# simastep.net
KiCad netlist of a schematic drawn in EAGLE
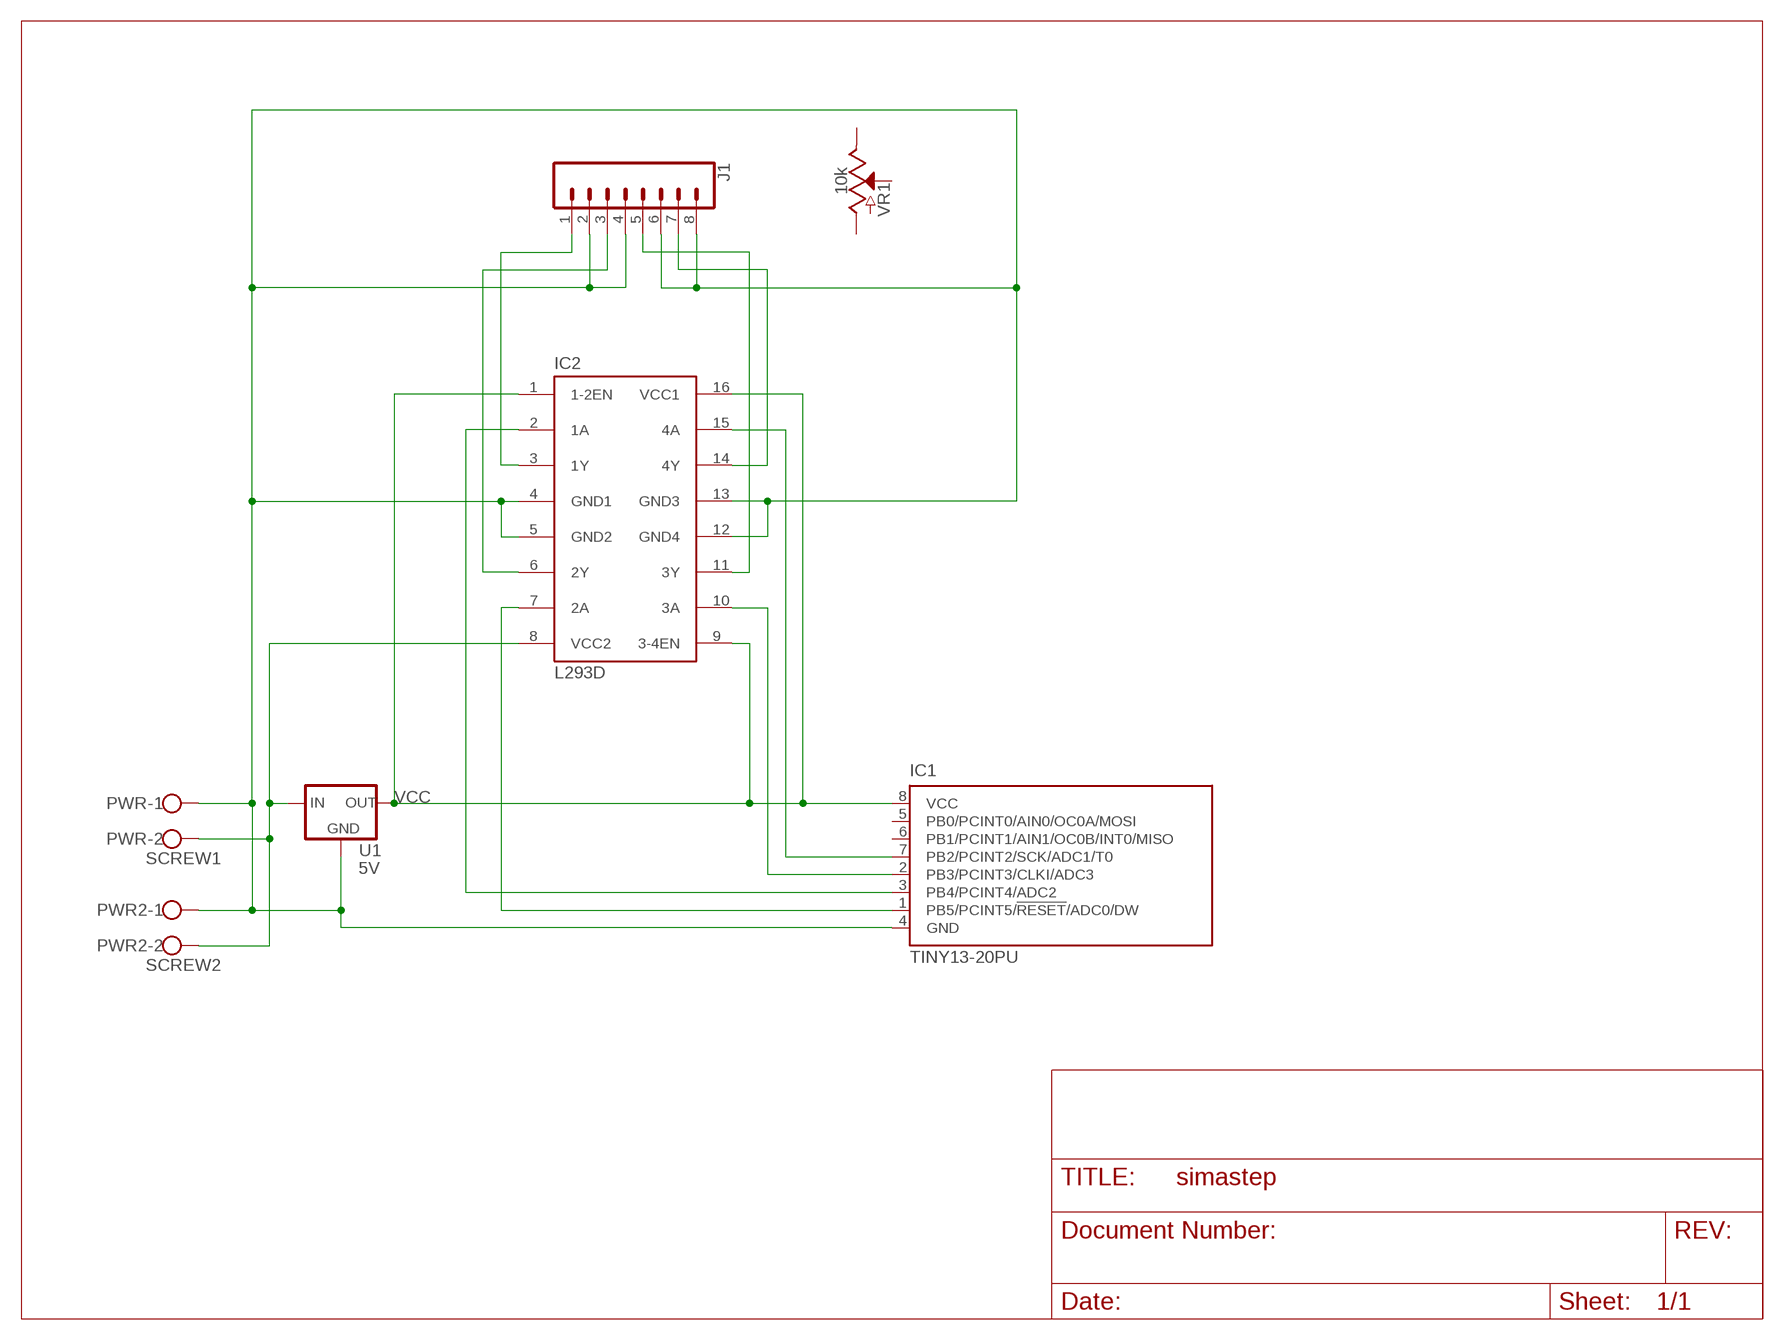
[diagram p0: schematic, sheet 1]

(export (version "E")
  (design (tool "Eeschema 10.0.6"))
  (components
    (comp (ref "IC1")
      (value "TINY13-20PU")
      (footprint "eagle-import:DIL08")
      (fields (field (name "MPN") "ATTINY13-20PU"))
      (libsource (lib "eagle-import") (part "TINY13PU-20"))
    )
    (comp (ref "IC2")
      (value "L293D")
      (footprint "eagle-import:DIL16")
      (libsource (lib "eagle-import") (part "L293D"))
    )
    (comp (ref "J1")
      (value "CONN_083.5MM-8")
      (footprint "eagle-import:SCREWTERMINAL-3.5MM-8")
      (libsource (lib "eagle-import") (part "CONN_083.5MM-8"))
    )
    (comp (ref "PWR")
      (value "SCREW1")
      (footprint "eagle-import:W237-102")
      (fields (field (name "MPN") "237-102"))
      (libsource (lib "eagle-import") (part "W237-102"))
    )
    (comp (ref "PWR2")
      (value "SCREW2")
      (footprint "eagle-import:W237-102")
      (fields (field (name "MPN") "237-102"))
      (libsource (lib "eagle-import") (part "W237-102"))
    )
    (comp (ref "U1")
      (value "5V")
      (footprint "eagle-import:TO220-IGO")
      (libsource (lib "eagle-import") (part "V_REG_78XXSINK"))
    )
    (comp (ref "VR1")
      (value "10k")
      (footprint "eagle-import:POT-PTH-ALPS")
      (libsource (lib "eagle-import") (part "POTENTIOMETER-PTH-9MM-1/20W-20%"))
    )
  )
  (nets
    (net (code "1") (name "/VCC") (class "Default")
      (node (ref "IC1") (pin "8") (pinfunction "VCC_8") (pintype "power_in"))
      (node (ref "IC2") (pin "1") (pinfunction "1-2EN_1") (pintype "input"))
      (node (ref "IC2") (pin "16") (pinfunction "VCC1_16") (pintype "power_in"))
      (node (ref "IC2") (pin "9") (pinfunction "3-4EN_9") (pintype "input"))
      (node (ref "U1") (pin "OUT") (pinfunction "OUT_OUT") (pintype "passive"))
    )
    (net (code "2") (name "Net-(IC1-GND)") (class "Default")
      (node (ref "IC1") (pin "4") (pinfunction "GND_4") (pintype "power_in"))
      (node (ref "IC2") (pin "12") (pinfunction "GND4_12") (pintype "power_in"))
      (node (ref "IC2") (pin "13") (pinfunction "GND3_13") (pintype "power_in"))
      (node (ref "IC2") (pin "4") (pinfunction "GND1_4") (pintype "power_in"))
      (node (ref "IC2") (pin "5") (pinfunction "GND2_5") (pintype "power_in"))
      (node (ref "J1") (pin "2") (pinfunction "2_2") (pintype "passive"))
      (node (ref "J1") (pin "4") (pinfunction "4_4") (pintype "passive"))
      (node (ref "J1") (pin "6") (pinfunction "6_6") (pintype "passive"))
      (node (ref "J1") (pin "8") (pinfunction "8_8") (pintype "passive"))
      (node (ref "PWR") (pin "1") (pinfunction "KL_1") (pintype "passive"))
      (node (ref "PWR2") (pin "1") (pinfunction "KL_1") (pintype "passive"))
      (node (ref "U1") (pin "GND") (pinfunction "GND_GND") (pintype "input"))
    )
    (net (code "3") (name "Net-(IC1-PB2{slash}PCINT2{slash}SCK{slash}ADC1{slash}T0)") (class "Default")
      (node (ref "IC1") (pin "7") (pinfunction "PB2/PCINT2/SCK/ADC1/T0_7") (pintype "bidirectional"))
      (node (ref "IC2") (pin "15") (pinfunction "4A_15") (pintype "input"))
    )
    (net (code "4") (name "Net-(IC1-PB3{slash}PCINT3{slash}CLKI{slash}ADC3)") (class "Default")
      (node (ref "IC1") (pin "2") (pinfunction "PB3/PCINT3/CLKI/ADC3_2") (pintype "bidirectional"))
      (node (ref "IC2") (pin "10") (pinfunction "3A_10") (pintype "input"))
    )
    (net (code "5") (name "Net-(IC1-PB4{slash}PCINT4{slash}ADC2)") (class "Default")
      (node (ref "IC1") (pin "3") (pinfunction "PB4/PCINT4/ADC2_3") (pintype "bidirectional"))
      (node (ref "IC2") (pin "2") (pinfunction "1A_2") (pintype "input"))
    )
    (net (code "6") (name "Net-(IC1-PB5{slash}PCINT5{slash}~{RESET}{slash}ADC0{slash}DW)") (class "Default")
      (node (ref "IC1") (pin "1") (pinfunction "PB5/PCINT5/~{RESET}/ADC0/DW_1") (pintype "bidirectional"))
      (node (ref "IC2") (pin "7") (pinfunction "2A_7") (pintype "input"))
    )
    (net (code "7") (name "Net-(IC2-1Y)") (class "Default")
      (node (ref "IC2") (pin "3") (pinfunction "1Y_3") (pintype "output"))
      (node (ref "J1") (pin "1") (pinfunction "1_1") (pintype "passive"))
    )
    (net (code "8") (name "Net-(IC2-2Y)") (class "Default")
      (node (ref "IC2") (pin "6") (pinfunction "2Y_6") (pintype "output"))
      (node (ref "J1") (pin "3") (pinfunction "3_3") (pintype "passive"))
    )
    (net (code "9") (name "Net-(IC2-3Y)") (class "Default")
      (node (ref "IC2") (pin "11") (pinfunction "3Y_11") (pintype "output"))
      (node (ref "J1") (pin "5") (pinfunction "5_5") (pintype "passive"))
    )
    (net (code "10") (name "Net-(IC2-4Y)") (class "Default")
      (node (ref "IC2") (pin "14") (pinfunction "4Y_14") (pintype "output"))
      (node (ref "J1") (pin "7") (pinfunction "7_7") (pintype "passive"))
    )
    (net (code "11") (name "Net-(IC2-VCC2)") (class "Default")
      (node (ref "IC2") (pin "8") (pinfunction "VCC2_8") (pintype "power_in"))
      (node (ref "PWR") (pin "2") (pinfunction "KL_2") (pintype "passive"))
      (node (ref "PWR2") (pin "2") (pinfunction "KL_2") (pintype "passive"))
      (node (ref "U1") (pin "IN") (pinfunction "IN_IN") (pintype "input"))
    )
    (net (code "12") (name "unconnected-(IC1-PB0{slash}PCINT0{slash}AIN0{slash}OC0A{slash}MOSI-Pad5)") (class "Default")
      (node (ref "IC1") (pin "5") (pinfunction "PB0/PCINT0/AIN0/OC0A/MOSI_5") (pintype "bidirectional"))
    )
    (net (code "13") (name "unconnected-(IC1-PB1{slash}PCINT1{slash}AIN1{slash}OC0B{slash}INT0{slash}MISO-Pad6)") (class "Default")
      (node (ref "IC1") (pin "6") (pinfunction "PB1/PCINT1/AIN1/OC0B/INT0/MISO_6") (pintype "bidirectional"))
    )
    (net (code "14") (name "unconnected-(VR1-A-PadP$3)") (class "Default")
      (node (ref "VR1") (pin "P$3") (pinfunction "A_P$3") (pintype "passive"))
    )
    (net (code "15") (name "unconnected-(VR1-E-PadP$1)") (class "Default")
      (node (ref "VR1") (pin "P$1") (pinfunction "E_P$1") (pintype "passive"))
    )
    (net (code "16") (name "unconnected-(VR1-S-PadP$2)") (class "Default")
      (node (ref "VR1") (pin "P$2") (pinfunction "S_P$2") (pintype "passive"))
    )
  )
)
